# rf_spectrum.net
KiCad netlist of a schematic drawn in EAGLE
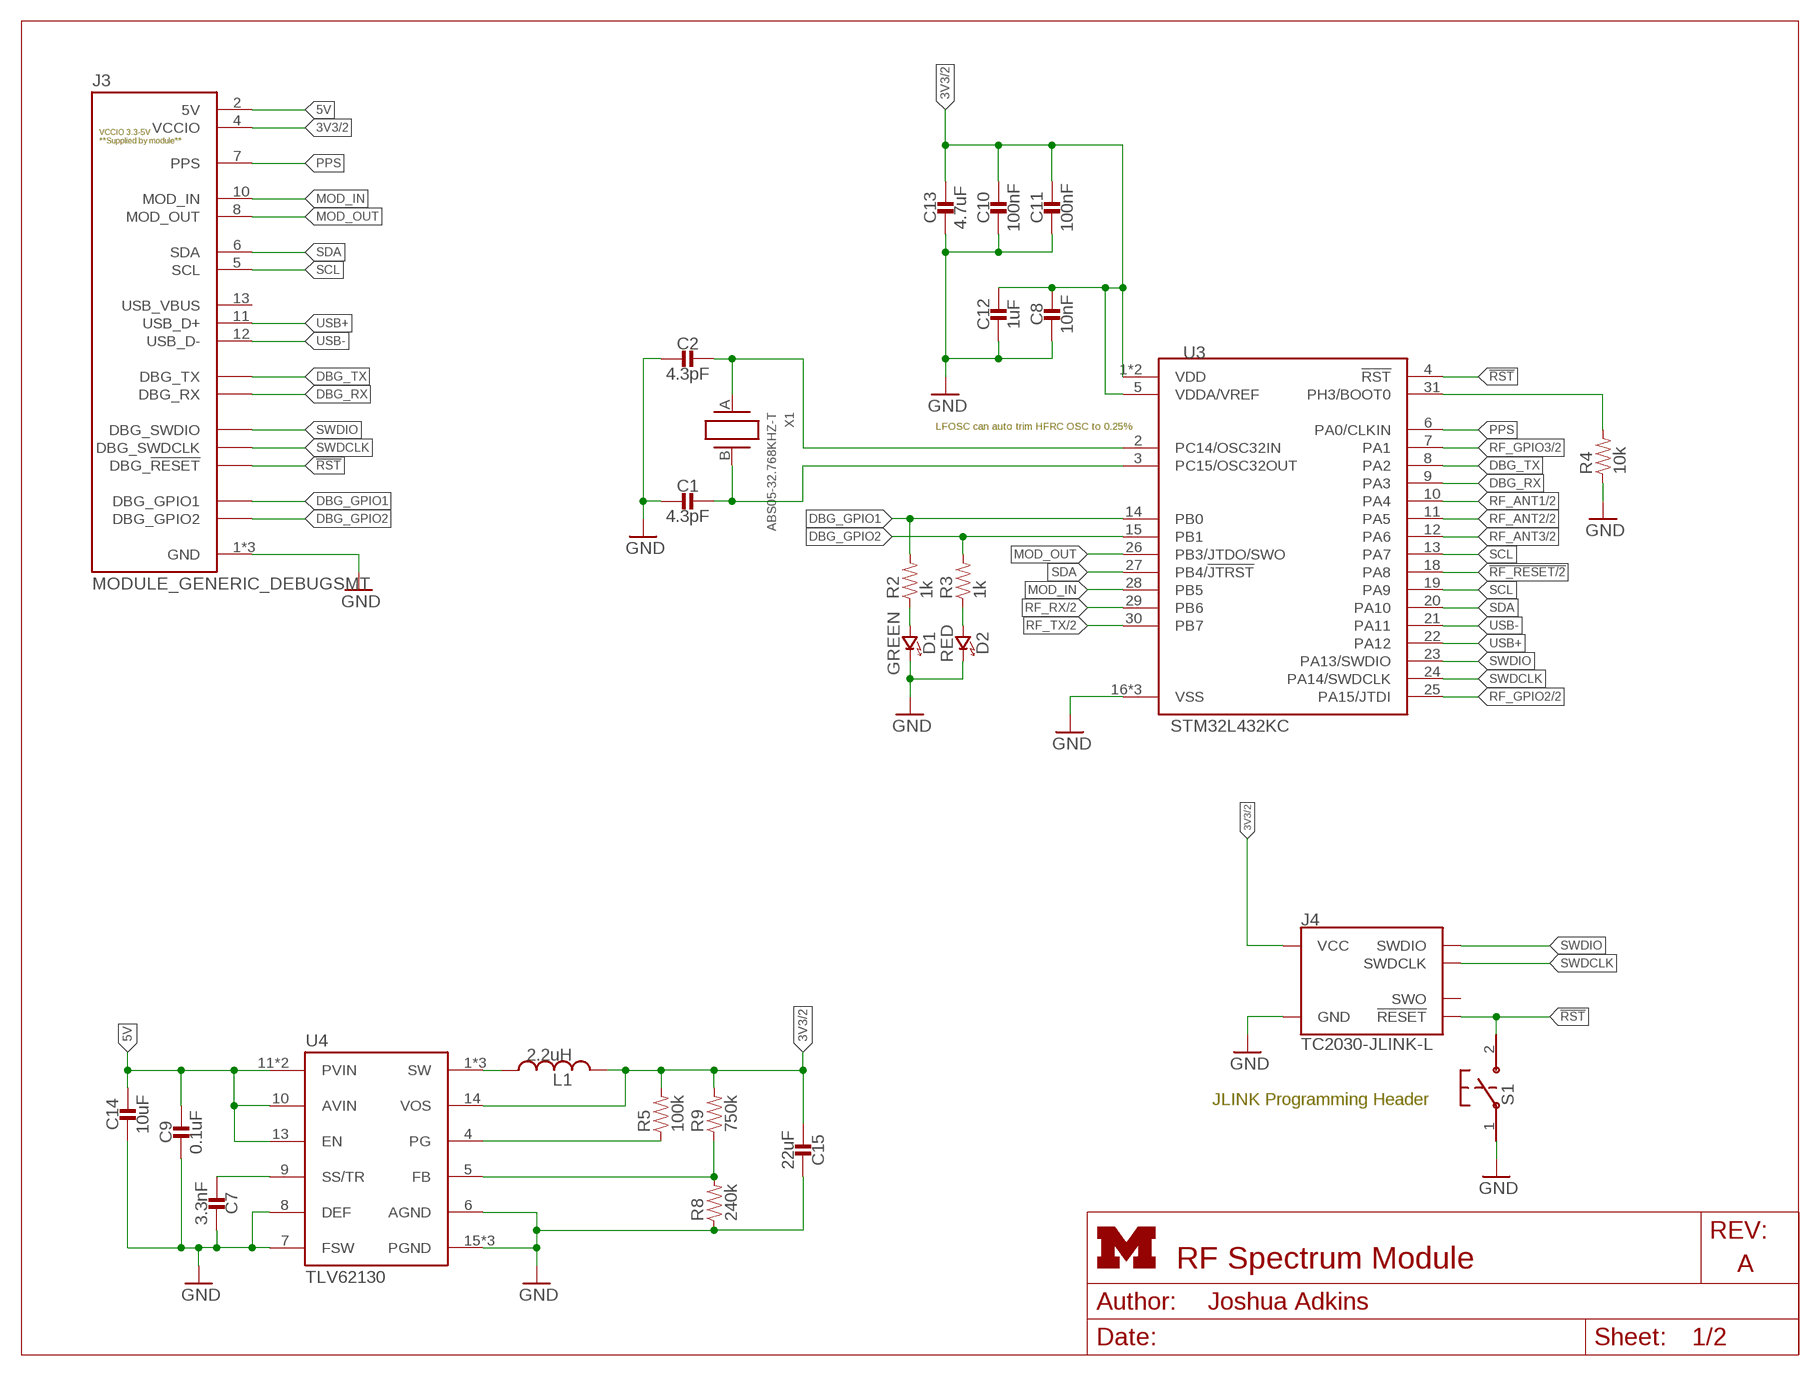
[diagram p0: schematic, sheet 1]
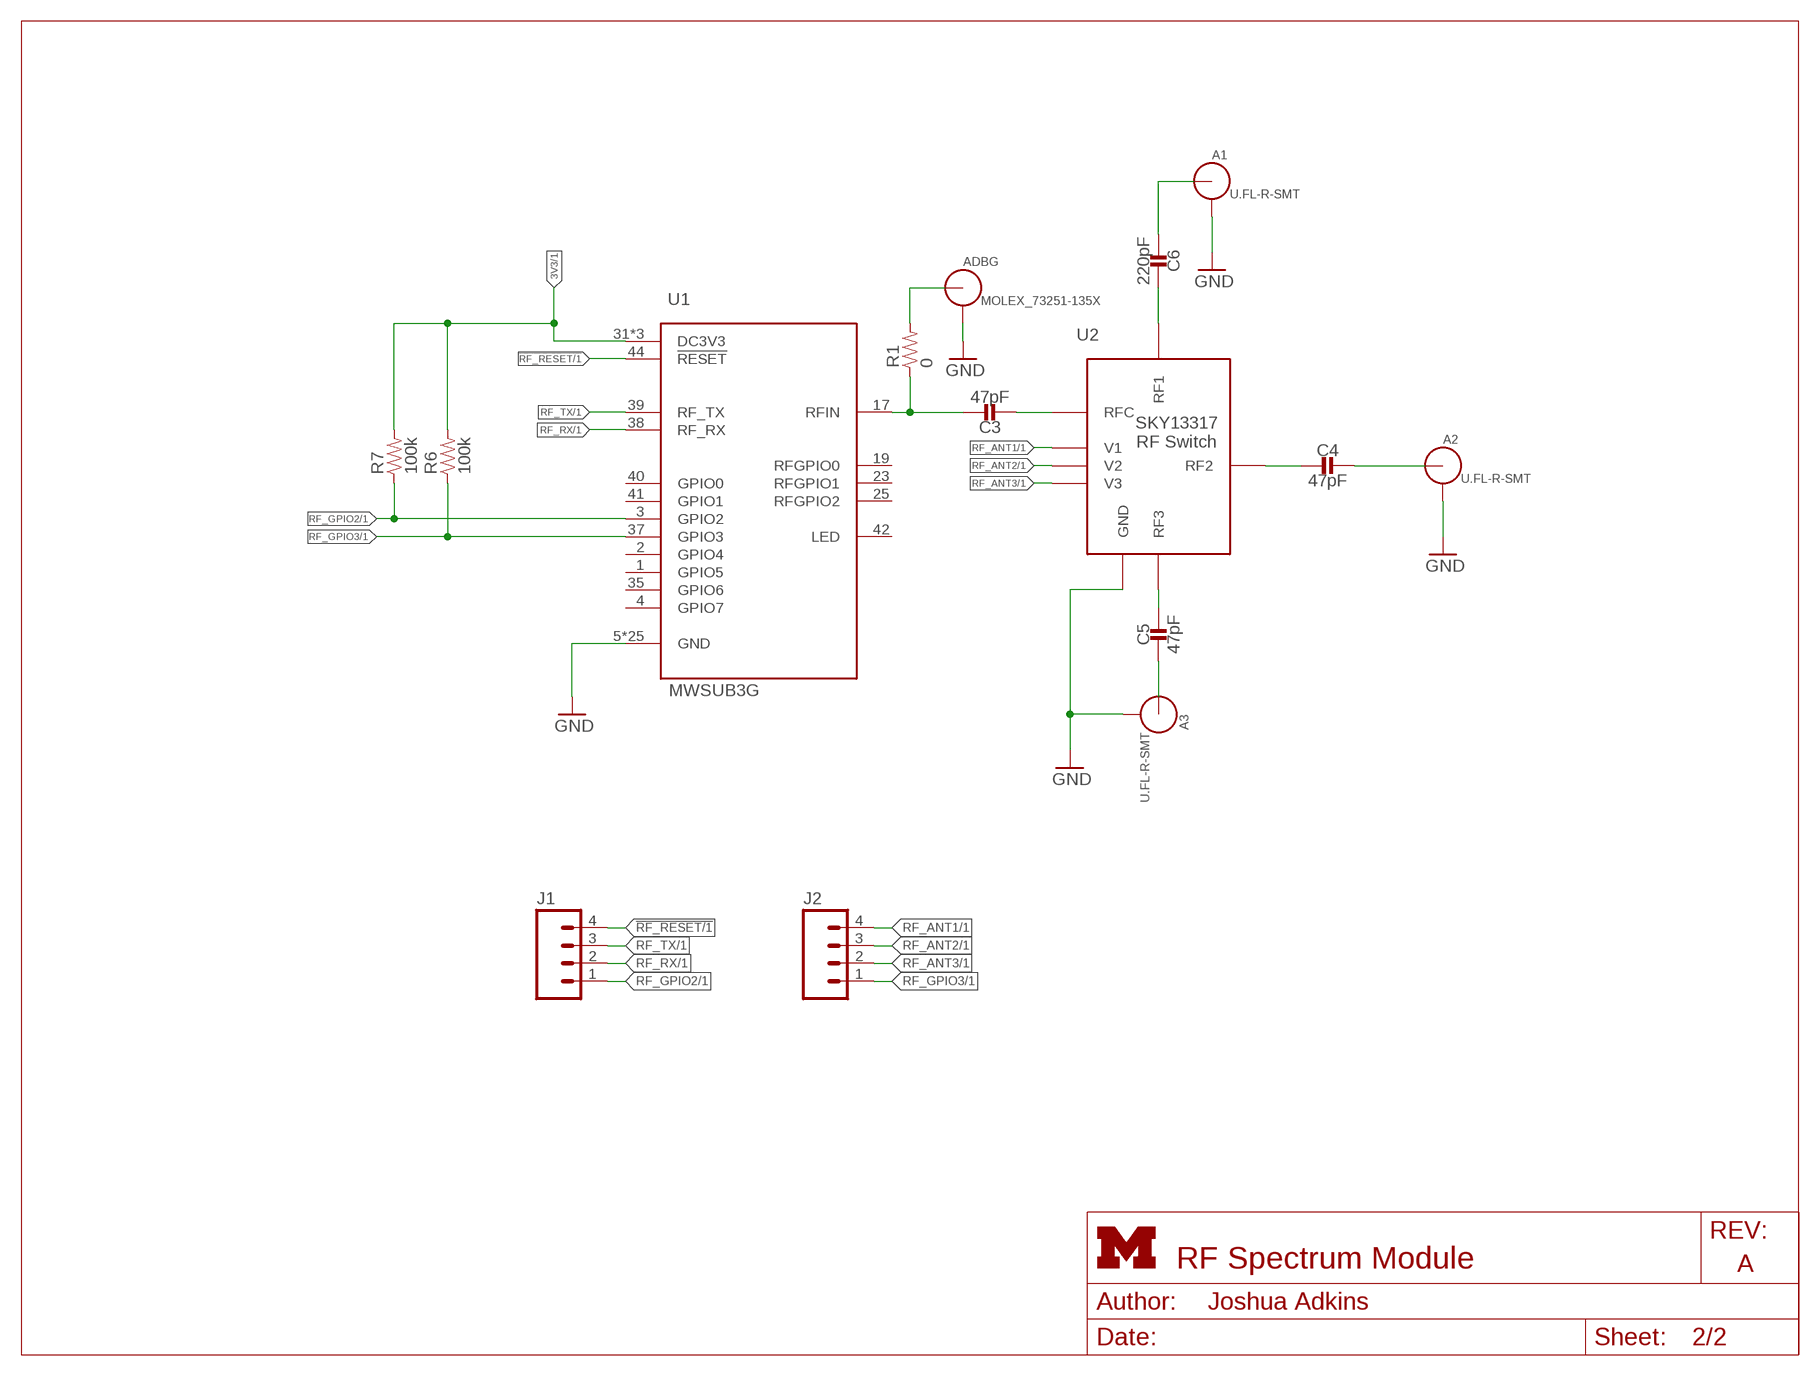
[diagram p1: schematic, sheet 2]

(export (version "E")
  (design (tool "Eeschema 10.0.6"))
  (components
    (comp (ref "A1")
      (value "U.FL-R-SMT")
      (footprint "eagle-import:U.FL_SMT")
      (libsource (lib "eagle-import") (part "U.FL-R-SMT"))
    )
    (comp (ref "A2")
      (value "U.FL-R-SMT")
      (footprint "eagle-import:U.FL_SMT")
      (libsource (lib "eagle-import") (part "U.FL-R-SMT"))
    )
    (comp (ref "A3")
      (value "U.FL-R-SMT")
      (footprint "eagle-import:U.FL_SMT")
      (libsource (lib "eagle-import") (part "U.FL-R-SMT"))
    )
    (comp (ref "ADBG")
      (value "MOLEX_73251-135X")
      (footprint "eagle-import:SMA-J_PCB")
      (libsource (lib "eagle-import") (part "MOLEX_73251-135X"))
    )
    (comp (ref "C3")
      (value "47pF")
      (footprint "eagle-import:0402_CAP")
      (fields (field (name "MF") "Murata"))
      (libsource (lib "eagle-import") (part "CAPACITOR0402_CAP"))
    )
    (comp (ref "C4")
      (value "47pF")
      (footprint "eagle-import:0402_CAP")
      (fields (field (name "MF") "Murata"))
      (libsource (lib "eagle-import") (part "CAPACITOR0402_CAP"))
    )
    (comp (ref "C5")
      (value "47pF")
      (footprint "eagle-import:0402_CAP")
      (fields (field (name "MF") "Murata"))
      (libsource (lib "eagle-import") (part "CAPACITOR0402_CAP"))
    )
    (comp (ref "C6")
      (value "220pF")
      (footprint "eagle-import:0402_CAP")
      (fields (field (name "MF") "Murata"))
      (libsource (lib "eagle-import") (part "CAPACITOR0402_CAP"))
    )
    (comp (ref "J1")
      (value "M04PTH")
      (footprint "eagle-import:1X04")
      (fields (field (name "MF") "Molex"))
      (libsource (lib "eagle-import") (part "M04PTH"))
    )
    (comp (ref "J2")
      (value "M04PTH")
      (footprint "eagle-import:1X04")
      (fields (field (name "MF") "Molex"))
      (libsource (lib "eagle-import") (part "M04PTH"))
    )
    (comp (ref "R1")
      (value "0")
      (footprint "eagle-import:0402_RES")
      (fields (field (name "MF") "Yageo"))
      (libsource (lib "eagle-import") (part "RESISTOR0402_RES"))
    )
    (comp (ref "R6")
      (value "100k")
      (footprint "eagle-import:0402_RES")
      (fields (field (name "MF") "Yageo"))
      (libsource (lib "eagle-import") (part "RESISTOR0402_RES"))
    )
    (comp (ref "R7")
      (value "100k")
      (footprint "eagle-import:0402_RES")
      (fields (field (name "MF") "Yageo"))
      (libsource (lib "eagle-import") (part "RESISTOR0402_RES"))
    )
    (comp (ref "U1")
      (value "MWSUB3G")
      (footprint "eagle-import:MWSUB3G")
      (fields (field (name "MF") "RFExplorer"))
      (libsource (lib "eagle-import") (part "MWSUB3G"))
    )
    (comp (ref "U2")
      (value "SKY13317")
      (footprint "eagle-import:XDFN-8")
      (libsource (lib "eagle-import") (part "SKY13317"))
    )
    (comp (ref "C1")
      (value "4.3pF")
      (footprint "eagle-import:0402_CAP")
      (fields (field (name "MF") "Murata"))
      (libsource (lib "eagle-import") (part "CAPACITOR0402_CAP"))
    )
    (comp (ref "C2")
      (value "4.3pF")
      (footprint "eagle-import:0402_CAP")
      (fields (field (name "MF") "Murata"))
      (libsource (lib "eagle-import") (part "CAPACITOR0402_CAP"))
    )
    (comp (ref "C7")
      (value "3.3nF")
      (footprint "eagle-import:0603_CAP")
      (fields (field (name "MF") "Murata"))
      (libsource (lib "eagle-import") (part "CAPACITOR0603_CAP"))
    )
    (comp (ref "C8")
      (value "10nF")
      (footprint "eagle-import:0402_CAP")
      (fields (field (name "MF") "Murata"))
      (libsource (lib "eagle-import") (part "CAPACITOR0402_CAP"))
    )
    (comp (ref "C9")
      (value "0.1uF")
      (footprint "eagle-import:0603_CAP")
      (fields (field (name "MF") "Murata"))
      (libsource (lib "eagle-import") (part "CAPACITOR0603_CAP"))
    )
    (comp (ref "C10")
      (value "100nF")
      (footprint "eagle-import:0402_CAP")
      (fields (field (name "MF") "Murata"))
      (libsource (lib "eagle-import") (part "CAPACITOR0402_CAP"))
    )
    (comp (ref "C11")
      (value "100nF")
      (footprint "eagle-import:0402_CAP")
      (fields (field (name "MF") "Murata"))
      (libsource (lib "eagle-import") (part "CAPACITOR0402_CAP"))
    )
    (comp (ref "C12")
      (value "1uF")
      (footprint "eagle-import:0402_CAP")
      (fields (field (name "MF") "Murata"))
      (libsource (lib "eagle-import") (part "CAPACITOR0402_CAP"))
    )
    (comp (ref "C13")
      (value "4.7uF")
      (footprint "eagle-import:0402_CAP")
      (fields (field (name "MF") "Murata"))
      (libsource (lib "eagle-import") (part "CAPACITOR0402_CAP"))
    )
    (comp (ref "C14")
      (value "10uF")
      (footprint "eagle-import:0603_CAP")
      (fields (field (name "MF") "Murata"))
      (libsource (lib "eagle-import") (part "CAPACITOR0603_CAP"))
    )
    (comp (ref "C15")
      (value "22uF")
      (footprint "eagle-import:0603_CAP")
      (fields (field (name "MF") "Murata"))
      (libsource (lib "eagle-import") (part "CAPACITOR0603_CAP"))
    )
    (comp (ref "D1")
      (value "GREEN")
      (footprint "eagle-import:LED-0603")
      (fields (field (name "MF") "Lite-ON"))
      (libsource (lib "eagle-import") (part "LED0603"))
    )
    (comp (ref "D2")
      (value "RED")
      (footprint "eagle-import:LED-0603")
      (fields (field (name "MF") "Lite-On"))
      (libsource (lib "eagle-import") (part "LED0603"))
    )
    (comp (ref "J3")
      (value "MODULE_GENERIC_DEBUGSMT")
      (footprint "eagle-import:MODULE_GENERIC_DEBUG_SMT")
      (libsource (lib "eagle-import") (part "MODULE_GENERIC_DEBUGSMT"))
    )
    (comp (ref "J4")
      (value "TC2030-JLINK-L")
      (footprint "eagle-import:TC2030-IDC")
      (libsource (lib "eagle-import") (part "TC2030-JLINK-L"))
    )
    (comp (ref "L1")
      (value "2.2uH")
      (footprint "eagle-import:IHL-1212BZ-11")
      (libsource (lib "eagle-import") (part "INDUCTORIHL"))
    )
    (comp (ref "R2")
      (value "1k")
      (footprint "eagle-import:0402_RES")
      (fields (field (name "MF") "Yageo"))
      (libsource (lib "eagle-import") (part "RESISTOR0402_RES"))
    )
    (comp (ref "R3")
      (value "1k")
      (footprint "eagle-import:0402_RES")
      (fields (field (name "MF") "Yageo"))
      (libsource (lib "eagle-import") (part "RESISTOR0402_RES"))
    )
    (comp (ref "R4")
      (value "10k")
      (footprint "eagle-import:0402_RES")
      (fields (field (name "MF") "Yageo"))
      (libsource (lib "eagle-import") (part "RESISTOR0402_RES"))
    )
    (comp (ref "R5")
      (value "100k")
      (footprint "eagle-import:0603-RES")
      (fields (field (name "MF") "Yageo"))
      (libsource (lib "eagle-import") (part "RESISTOR0603_RES"))
    )
    (comp (ref "R8")
      (value "240k")
      (footprint "eagle-import:0603-RES")
      (fields (field (name "MF") "Yageo"))
      (libsource (lib "eagle-import") (part "RESISTOR0603_RES"))
    )
    (comp (ref "R9")
      (value "750k")
      (footprint "eagle-import:0603-RES")
      (fields (field (name "MF") "Yageo"))
      (libsource (lib "eagle-import") (part "RESISTOR0603_RES"))
    )
    (comp (ref "S1")
      (value "B3U-1000P")
      (footprint "eagle-import:B3U-1000P")
      (libsource (lib "eagle-import") (part "B3U-1000P"))
    )
    (comp (ref "U3")
      (value "STM32L432KC")
      (footprint "eagle-import:UQFN-32")
      (fields (field (name "MF") "STM"))
      (libsource (lib "eagle-import") (part "STM32L432KC"))
    )
    (comp (ref "U4")
      (value "TLV62130")
      (footprint "eagle-import:TQFN-16_3MM")
      (libsource (lib "eagle-import") (part "TLV62130"))
    )
    (comp (ref "X1")
      (value "ABS05-32.768KHZ-T")
      (footprint "eagle-import:ABS05")
      (libsource (lib "eagle-import") (part "ABS05-32.768KHZ-T"))
    )
  )
  (nets
    (net (code "1") (name "3V3") (class "Default")
      (node (ref "C10") (pin "1") (pinfunction "1_1") (pintype "bidirectional"))
      (node (ref "C11") (pin "1") (pinfunction "1_1") (pintype "bidirectional"))
      (node (ref "C12") (pin "1") (pinfunction "1_1") (pintype "bidirectional"))
      (node (ref "C13") (pin "1") (pinfunction "1_1") (pintype "bidirectional"))
      (node (ref "C15") (pin "2") (pinfunction "2_2") (pintype "bidirectional"))
      (node (ref "C8") (pin "1") (pinfunction "1_1") (pintype "bidirectional"))
      (node (ref "J3") (pin "4") (pinfunction "VCCIO_4") (pintype "bidirectional"))
      (node (ref "J4") (pin "1") (pinfunction "VCC_1") (pintype "bidirectional"))
      (node (ref "L1") (pin "P$2") (pinfunction "2_P$2") (pintype "bidirectional"))
      (node (ref "R5") (pin "2") (pinfunction "2_2") (pintype "passive"))
      (node (ref "R6") (pin "2") (pinfunction "2_2") (pintype "passive"))
      (node (ref "R7") (pin "2") (pinfunction "2_2") (pintype "passive"))
      (node (ref "R9") (pin "2") (pinfunction "2_2") (pintype "passive"))
      (node (ref "U1") (pin "31") (pinfunction "DC3V3_31") (pintype "bidirectional"))
      (node (ref "U1") (pin "32") (pinfunction "DC3V3_32") (pintype "bidirectional"))
      (node (ref "U1") (pin "33") (pinfunction "DC3V3_33") (pintype "bidirectional"))
      (node (ref "U3") (pin "1") (pinfunction "VDD_1") (pintype "bidirectional"))
      (node (ref "U3") (pin "17") (pinfunction "VDD_17") (pintype "bidirectional"))
      (node (ref "U3") (pin "5") (pinfunction "VDDA/VREF_5") (pintype "bidirectional"))
      (node (ref "U4") (pin "14") (pinfunction "VOS_14") (pintype "bidirectional"))
    )
    (net (code "2") (name "5V") (class "Default")
      (node (ref "C14") (pin "1") (pinfunction "1_1") (pintype "bidirectional"))
      (node (ref "C9") (pin "1") (pinfunction "1_1") (pintype "bidirectional"))
      (node (ref "J3") (pin "2") (pinfunction "5V_2") (pintype "bidirectional"))
      (node (ref "U4") (pin "10") (pinfunction "AVIN_10") (pintype "bidirectional"))
      (node (ref "U4") (pin "11") (pinfunction "PVIN_11") (pintype "bidirectional"))
      (node (ref "U4") (pin "12") (pinfunction "PVIN_12") (pintype "bidirectional"))
      (node (ref "U4") (pin "13") (pinfunction "EN_13") (pintype "bidirectional"))
    )
    (net (code "3") (name "DBG_GPIO1") (class "Default")
      (node (ref "J3") (pin "16") (pinfunction "DBG_GPIO1_16") (pintype "bidirectional"))
      (node (ref "R2") (pin "2") (pinfunction "2_2") (pintype "passive"))
      (node (ref "U3") (pin "14") (pinfunction "PB0_14") (pintype "bidirectional"))
    )
    (net (code "4") (name "DBG_GPIO2") (class "Default")
      (node (ref "J3") (pin "19") (pinfunction "DBG_GPIO2_19") (pintype "bidirectional"))
      (node (ref "R3") (pin "2") (pinfunction "2_2") (pintype "passive"))
      (node (ref "U3") (pin "15") (pinfunction "PB1_15") (pintype "bidirectional"))
    )
    (net (code "5") (name "DBG_RX") (class "Default")
      (node (ref "J3") (pin "18") (pinfunction "DBG_RX_18") (pintype "bidirectional"))
      (node (ref "U3") (pin "9") (pinfunction "PA3_9") (pintype "bidirectional"))
    )
    (net (code "6") (name "DBG_TX") (class "Default")
      (node (ref "J3") (pin "17") (pinfunction "DBG_TX_17") (pintype "bidirectional"))
      (node (ref "U3") (pin "8") (pinfunction "PA2_8") (pintype "bidirectional"))
    )
    (net (code "7") (name "GND") (class "Default")
      (node (ref "A1") (pin "GND1") (pinfunction "P$2_GND1") (pintype "bidirectional"))
      (node (ref "A1") (pin "GND2") (pinfunction "P$2_GND2") (pintype "bidirectional"))
      (node (ref "A2") (pin "GND1") (pinfunction "P$2_GND1") (pintype "bidirectional"))
      (node (ref "A2") (pin "GND2") (pinfunction "P$2_GND2") (pintype "bidirectional"))
      (node (ref "A3") (pin "GND1") (pinfunction "P$2_GND1") (pintype "bidirectional"))
      (node (ref "A3") (pin "GND2") (pinfunction "P$2_GND2") (pintype "bidirectional"))
      (node (ref "ADBG") (pin "2") (pinfunction "P$2_2") (pintype "bidirectional"))
      (node (ref "ADBG") (pin "3") (pinfunction "P$2_3") (pintype "bidirectional"))
      (node (ref "ADBG") (pin "4") (pinfunction "P$2_4") (pintype "bidirectional"))
      (node (ref "ADBG") (pin "5") (pinfunction "P$2_5") (pintype "bidirectional"))
      (node (ref "C1") (pin "2") (pinfunction "2_2") (pintype "bidirectional"))
      (node (ref "C10") (pin "2") (pinfunction "2_2") (pintype "bidirectional"))
      (node (ref "C11") (pin "2") (pinfunction "2_2") (pintype "bidirectional"))
      (node (ref "C12") (pin "2") (pinfunction "2_2") (pintype "bidirectional"))
      (node (ref "C13") (pin "2") (pinfunction "2_2") (pintype "bidirectional"))
      (node (ref "C14") (pin "2") (pinfunction "2_2") (pintype "bidirectional"))
      (node (ref "C15") (pin "1") (pinfunction "1_1") (pintype "bidirectional"))
      (node (ref "C2") (pin "2") (pinfunction "2_2") (pintype "bidirectional"))
      (node (ref "C7") (pin "1") (pinfunction "1_1") (pintype "bidirectional"))
      (node (ref "C8") (pin "2") (pinfunction "2_2") (pintype "bidirectional"))
      (node (ref "C9") (pin "2") (pinfunction "2_2") (pintype "bidirectional"))
      (node (ref "D1") (pin "C") (pinfunction "CATHODE_C") (pintype "bidirectional"))
      (node (ref "D2") (pin "C") (pinfunction "CATHODE_C") (pintype "bidirectional"))
      (node (ref "J3") (pin "1") (pinfunction "GND_1") (pintype "bidirectional"))
      (node (ref "J3") (pin "14") (pinfunction "GND_14") (pintype "bidirectional"))
      (node (ref "J3") (pin "15") (pinfunction "GND_15") (pintype "bidirectional"))
      (node (ref "J4") (pin "5") (pinfunction "GND_5") (pintype "bidirectional"))
      (node (ref "R4") (pin "1") (pinfunction "1_1") (pintype "passive"))
      (node (ref "R8") (pin "1") (pinfunction "1_1") (pintype "passive"))
      (node (ref "S1") (pin "1") (pinfunction "P$1_1") (pintype "passive"))
      (node (ref "U1") (pin "10") (pinfunction "GND_10") (pintype "bidirectional"))
      (node (ref "U1") (pin "11") (pinfunction "GND_11") (pintype "bidirectional"))
      (node (ref "U1") (pin "12") (pinfunction "GND_12") (pintype "bidirectional"))
      (node (ref "U1") (pin "13") (pinfunction "GND_13") (pintype "bidirectional"))
      (node (ref "U1") (pin "14") (pinfunction "GND_14") (pintype "bidirectional"))
      (node (ref "U1") (pin "15") (pinfunction "GND_15") (pintype "bidirectional"))
      (node (ref "U1") (pin "16") (pinfunction "GND_16") (pintype "bidirectional"))
      (node (ref "U1") (pin "18") (pinfunction "GND_18") (pintype "bidirectional"))
      (node (ref "U1") (pin "20") (pinfunction "GND_20") (pintype "bidirectional"))
      (node (ref "U1") (pin "21") (pinfunction "GND_21") (pintype "bidirectional"))
      (node (ref "U1") (pin "22") (pinfunction "GND_22") (pintype "bidirectional"))
      (node (ref "U1") (pin "24") (pinfunction "GND_24") (pintype "bidirectional"))
      (node (ref "U1") (pin "26") (pinfunction "GND_26") (pintype "bidirectional"))
      (node (ref "U1") (pin "27") (pinfunction "GND_27") (pintype "bidirectional"))
      (node (ref "U1") (pin "28") (pinfunction "GND_28") (pintype "bidirectional"))
      (node (ref "U1") (pin "29") (pinfunction "GND_29") (pintype "bidirectional"))
      (node (ref "U1") (pin "34") (pinfunction "GND_34") (pintype "bidirectional"))
      (node (ref "U1") (pin "43") (pinfunction "GND_43") (pintype "bidirectional"))
      (node (ref "U1") (pin "45") (pinfunction "GND_45") (pintype "bidirectional"))
      (node (ref "U1") (pin "46") (pinfunction "GND_46") (pintype "bidirectional"))
      (node (ref "U1") (pin "5") (pinfunction "GND_5") (pintype "bidirectional"))
      (node (ref "U1") (pin "6") (pinfunction "GND_6") (pintype "bidirectional"))
      (node (ref "U1") (pin "7") (pinfunction "GND_7") (pintype "bidirectional"))
      (node (ref "U1") (pin "8") (pinfunction "GND_8") (pintype "bidirectional"))
      (node (ref "U1") (pin "9") (pinfunction "GND_9") (pintype "bidirectional"))
      (node (ref "U2") (pin "P$1") (pinfunction "GND_P$1") (pintype "bidirectional"))
      (node (ref "U3") (pin "16") (pinfunction "VSS_16") (pintype "bidirectional"))
      (node (ref "U3") (pin "32") (pinfunction "VSS_32") (pintype "bidirectional"))
      (node (ref "U3") (pin "THERMAL") (pinfunction "VSS_THERMAL") (pintype "bidirectional"))
      (node (ref "U4") (pin "15") (pinfunction "PGND_15") (pintype "bidirectional"))
      (node (ref "U4") (pin "16") (pinfunction "PGND_16") (pintype "bidirectional"))
      (node (ref "U4") (pin "6") (pinfunction "AGND_6") (pintype "bidirectional"))
      (node (ref "U4") (pin "7") (pinfunction "FSW_7") (pintype "bidirectional"))
      (node (ref "U4") (pin "8") (pinfunction "DEF_8") (pintype "bidirectional"))
      (node (ref "U4") (pin "GND") (pinfunction "PGND_GND") (pintype "bidirectional"))
    )
    (net (code "8") (name "MOD_IN") (class "Default")
      (node (ref "J3") (pin "10") (pinfunction "MOD_IN_10") (pintype "bidirectional"))
      (node (ref "U3") (pin "28") (pinfunction "PB5_28") (pintype "bidirectional"))
    )
    (net (code "9") (name "MOD_OUT") (class "Default")
      (node (ref "J3") (pin "8") (pinfunction "MOD_OUT_8") (pintype "bidirectional"))
      (node (ref "U3") (pin "26") (pinfunction "PB3/JTDO/SWO_26") (pintype "bidirectional"))
    )
    (net (code "10") (name "Net-(A1-ANT)") (class "Default")
      (node (ref "A1") (pin "SIG") (pinfunction "ANT_SIG") (pintype "bidirectional"))
      (node (ref "C6") (pin "2") (pinfunction "2_2") (pintype "bidirectional"))
    )
    (net (code "11") (name "Net-(A2-ANT)") (class "Default")
      (node (ref "A2") (pin "SIG") (pinfunction "ANT_SIG") (pintype "bidirectional"))
      (node (ref "C4") (pin "1") (pinfunction "1_1") (pintype "bidirectional"))
    )
    (net (code "12") (name "Net-(A3-ANT)") (class "Default")
      (node (ref "A3") (pin "SIG") (pinfunction "ANT_SIG") (pintype "bidirectional"))
      (node (ref "C5") (pin "2") (pinfunction "2_2") (pintype "bidirectional"))
    )
    (net (code "13") (name "Net-(ADBG-ANT)") (class "Default")
      (node (ref "ADBG") (pin "1") (pinfunction "ANT_1") (pintype "bidirectional"))
      (node (ref "R1") (pin "2") (pinfunction "2_2") (pintype "passive"))
    )
    (net (code "14") (name "Net-(D1-ANODE)") (class "Default")
      (node (ref "D1") (pin "A") (pinfunction "ANODE_A") (pintype "bidirectional"))
      (node (ref "R2") (pin "1") (pinfunction "1_1") (pintype "passive"))
    )
    (net (code "15") (name "Net-(D2-ANODE)") (class "Default")
      (node (ref "D2") (pin "A") (pinfunction "ANODE_A") (pintype "bidirectional"))
      (node (ref "R3") (pin "1") (pinfunction "1_1") (pintype "passive"))
    )
    (net (code "16") (name "Net-(L1-1)") (class "Default")
      (node (ref "L1") (pin "P$1") (pinfunction "1_P$1") (pintype "bidirectional"))
      (node (ref "U4") (pin "1") (pinfunction "SW_1") (pintype "bidirectional"))
      (node (ref "U4") (pin "2") (pinfunction "SW_2") (pintype "bidirectional"))
      (node (ref "U4") (pin "3") (pinfunction "SW_3") (pintype "bidirectional"))
    )
    (net (code "17") (name "Net-(U1-RFIN)") (class "Default")
      (node (ref "C3") (pin "1") (pinfunction "1_1") (pintype "bidirectional"))
      (node (ref "R1") (pin "1") (pinfunction "1_1") (pintype "passive"))
      (node (ref "U1") (pin "17") (pinfunction "RFIN_17") (pintype "bidirectional"))
    )
    (net (code "18") (name "Net-(U2-RF1)") (class "Default")
      (node (ref "C6") (pin "1") (pinfunction "1_1") (pintype "bidirectional"))
      (node (ref "U2") (pin "4") (pinfunction "RF1_4") (pintype "bidirectional"))
    )
    (net (code "19") (name "Net-(U2-RF2)") (class "Default")
      (node (ref "C4") (pin "2") (pinfunction "2_2") (pintype "bidirectional"))
      (node (ref "U2") (pin "5") (pinfunction "RF2_5") (pintype "bidirectional"))
    )
    (net (code "20") (name "Net-(U2-RF3)") (class "Default")
      (node (ref "C5") (pin "1") (pinfunction "1_1") (pintype "bidirectional"))
      (node (ref "U2") (pin "8") (pinfunction "RF3_8") (pintype "bidirectional"))
    )
    (net (code "21") (name "Net-(U2-RFC)") (class "Default")
      (node (ref "C3") (pin "2") (pinfunction "2_2") (pintype "bidirectional"))
      (node (ref "U2") (pin "1") (pinfunction "RFC_1") (pintype "bidirectional"))
    )
    (net (code "22") (name "Net-(U3-PC14{slash}OSC32IN)") (class "Default")
      (node (ref "C2") (pin "1") (pinfunction "1_1") (pintype "bidirectional"))
      (node (ref "U3") (pin "2") (pinfunction "PC14/OSC32IN_2") (pintype "bidirectional"))
      (node (ref "X1") (pin "A") (pinfunction "1_A") (pintype "bidirectional"))
    )
    (net (code "23") (name "Net-(U3-PC15{slash}OSC32OUT)") (class "Default")
      (node (ref "C1") (pin "1") (pinfunction "1_1") (pintype "bidirectional"))
      (node (ref "U3") (pin "3") (pinfunction "PC15/OSC32OUT_3") (pintype "bidirectional"))
      (node (ref "X1") (pin "B") (pinfunction "2_B") (pintype "bidirectional"))
    )
    (net (code "24") (name "Net-(U3-PH3{slash}BOOT0)") (class "Default")
      (node (ref "R4") (pin "2") (pinfunction "2_2") (pintype "passive"))
      (node (ref "U3") (pin "31") (pinfunction "PH3/BOOT0_31") (pintype "bidirectional"))
    )
    (net (code "25") (name "Net-(U4-FB)") (class "Default")
      (node (ref "R8") (pin "2") (pinfunction "2_2") (pintype "passive"))
      (node (ref "R9") (pin "1") (pinfunction "1_1") (pintype "passive"))
      (node (ref "U4") (pin "5") (pinfunction "FB_5") (pintype "bidirectional"))
    )
    (net (code "26") (name "Net-(U4-PG)") (class "Default")
      (node (ref "R5") (pin "1") (pinfunction "1_1") (pintype "passive"))
      (node (ref "U4") (pin "4") (pinfunction "PG_4") (pintype "bidirectional"))
    )
    (net (code "27") (name "Net-(U4-SS{slash}TR)") (class "Default")
      (node (ref "C7") (pin "2") (pinfunction "2_2") (pintype "bidirectional"))
      (node (ref "U4") (pin "9") (pinfunction "SS/TR_9") (pintype "bidirectional"))
    )
    (net (code "28") (name "PPS") (class "Default")
      (node (ref "J3") (pin "7") (pinfunction "PPS_7") (pintype "bidirectional"))
      (node (ref "U3") (pin "6") (pinfunction "PA0/CLKIN_6") (pintype "bidirectional"))
    )
    (net (code "29") (name "RF_ANT1") (class "Default")
      (node (ref "J2") (pin "4") (pinfunction "4_4") (pintype "passive"))
      (node (ref "U2") (pin "3") (pinfunction "V1_3") (pintype "bidirectional"))
      (node (ref "U3") (pin "10") (pinfunction "PA4_10") (pintype "bidirectional"))
    )
    (net (code "30") (name "RF_ANT2") (class "Default")
      (node (ref "J2") (pin "3") (pinfunction "3_3") (pintype "passive"))
      (node (ref "U2") (pin "6") (pinfunction "V2_6") (pintype "bidirectional"))
      (node (ref "U3") (pin "11") (pinfunction "PA5_11") (pintype "bidirectional"))
    )
    (net (code "31") (name "RF_ANT3") (class "Default")
      (node (ref "J2") (pin "2") (pinfunction "2_2") (pintype "passive"))
      (node (ref "U2") (pin "7") (pinfunction "V3_7") (pintype "bidirectional"))
      (node (ref "U3") (pin "12") (pinfunction "PA6_12") (pintype "bidirectional"))
    )
    (net (code "32") (name "RF_GPIO2") (class "Default")
      (node (ref "J1") (pin "1") (pinfunction "1_1") (pintype "passive"))
      (node (ref "R7") (pin "1") (pinfunction "1_1") (pintype "passive"))
      (node (ref "U1") (pin "3") (pinfunction "GPIO2_3") (pintype "bidirectional"))
      (node (ref "U3") (pin "25") (pinfunction "PA15/JTDI_25") (pintype "bidirectional"))
    )
    (net (code "33") (name "RF_GPIO3") (class "Default")
      (node (ref "J2") (pin "1") (pinfunction "1_1") (pintype "passive"))
      (node (ref "R6") (pin "1") (pinfunction "1_1") (pintype "passive"))
      (node (ref "U1") (pin "37") (pinfunction "GPIO3_37") (pintype "bidirectional"))
      (node (ref "U3") (pin "7") (pinfunction "PA1_7") (pintype "bidirectional"))
    )
    (net (code "34") (name "RF_RX") (class "Default")
      (node (ref "J1") (pin "2") (pinfunction "2_2") (pintype "passive"))
      (node (ref "U1") (pin "38") (pinfunction "RF_RX_38") (pintype "bidirectional"))
      (node (ref "U3") (pin "29") (pinfunction "PB6_29") (pintype "bidirectional"))
    )
    (net (code "35") (name "RF_TX") (class "Default")
      (node (ref "J1") (pin "3") (pinfunction "3_3") (pintype "passive"))
      (node (ref "U1") (pin "39") (pinfunction "RF_TX_39") (pintype "bidirectional"))
      (node (ref "U3") (pin "30") (pinfunction "PB7_30") (pintype "bidirectional"))
    )
    (net (code "36") (name "SCL") (class "Default")
      (node (ref "J3") (pin "5") (pinfunction "SCL_5") (pintype "bidirectional"))
      (node (ref "U3") (pin "13") (pinfunction "PA7_13") (pintype "bidirectional"))
      (node (ref "U3") (pin "19") (pinfunction "PA9_19") (pintype "bidirectional"))
    )
    (net (code "37") (name "SDA") (class "Default")
      (node (ref "J3") (pin "6") (pinfunction "SDA_6") (pintype "bidirectional"))
      (node (ref "U3") (pin "20") (pinfunction "PA10_20") (pintype "bidirectional"))
      (node (ref "U3") (pin "27") (pinfunction "PB4/~{JTRST}_27") (pintype "bidirectional"))
    )
    (net (code "38") (name "SWDCLK") (class "Default")
      (node (ref "J3") (pin "21") (pinfunction "DBG_SWDCLK_21") (pintype "bidirectional"))
      (node (ref "J4") (pin "4") (pinfunction "SWDCLK_4") (pintype "bidirectional"))
      (node (ref "U3") (pin "24") (pinfunction "PA14/SWDCLK_24") (pintype "bidirectional"))
    )
    (net (code "39") (name "SWDIO") (class "Default")
      (node (ref "J3") (pin "22") (pinfunction "DBG_SWDIO_22") (pintype "bidirectional"))
      (node (ref "J4") (pin "2") (pinfunction "SWDIO_2") (pintype "bidirectional"))
      (node (ref "U3") (pin "23") (pinfunction "PA13/SWDIO_23") (pintype "bidirectional"))
    )
    (net (code "40") (name "USB+") (class "Default")
      (node (ref "J3") (pin "11") (pinfunction "USB_D+_11") (pintype "bidirectional"))
      (node (ref "U3") (pin "22") (pinfunction "PA12_22") (pintype "bidirectional"))
    )
    (net (code "41") (name "USB-") (class "Default")
      (node (ref "J3") (pin "12") (pinfunction "USB_D-_12") (pintype "bidirectional"))
      (node (ref "U3") (pin "21") (pinfunction "PA11_21") (pintype "bidirectional"))
    )
    (net (code "42") (name "unconnected-(J3-USB_VBUS-Pad13)") (class "Default")
      (node (ref "J3") (pin "13") (pinfunction "USB_VBUS_13") (pintype "bidirectional"))
    )
    (net (code "43") (name "unconnected-(J4-SWO-Pad6)") (class "Default")
      (node (ref "J4") (pin "6") (pinfunction "SWO_6") (pintype "bidirectional"))
    )
    (net (code "44") (name "unconnected-(U1-GPIO0-Pad40)") (class "Default")
      (node (ref "U1") (pin "40") (pinfunction "GPIO0_40") (pintype "bidirectional"))
    )
    (net (code "45") (name "unconnected-(U1-GPIO1-Pad41)") (class "Default")
      (node (ref "U1") (pin "41") (pinfunction "GPIO1_41") (pintype "bidirectional"))
    )
    (net (code "46") (name "unconnected-(U1-GPIO4-Pad2)") (class "Default")
      (node (ref "U1") (pin "2") (pinfunction "GPIO4_2") (pintype "bidirectional"))
    )
    (net (code "47") (name "unconnected-(U1-GPIO5-Pad1)") (class "Default")
      (node (ref "U1") (pin "1") (pinfunction "GPIO5_1") (pintype "bidirectional"))
    )
    (net (code "48") (name "unconnected-(U1-GPIO6-Pad35)") (class "Default")
      (node (ref "U1") (pin "35") (pinfunction "GPIO6_35") (pintype "bidirectional"))
    )
    (net (code "49") (name "unconnected-(U1-GPIO7-Pad4)") (class "Default")
      (node (ref "U1") (pin "4") (pinfunction "GPIO7_4") (pintype "bidirectional"))
    )
    (net (code "50") (name "unconnected-(U1-LED-Pad42)") (class "Default")
      (node (ref "U1") (pin "42") (pinfunction "LED_42") (pintype "bidirectional"))
    )
    (net (code "51") (name "unconnected-(U1-RFGPIO0-Pad19)") (class "Default")
      (node (ref "U1") (pin "19") (pinfunction "RFGPIO0_19") (pintype "bidirectional"))
    )
    (net (code "52") (name "unconnected-(U1-RFGPIO1-Pad23)") (class "Default")
      (node (ref "U1") (pin "23") (pinfunction "RFGPIO1_23") (pintype "bidirectional"))
    )
    (net (code "53") (name "unconnected-(U1-RFGPIO2-Pad25)") (class "Default")
      (node (ref "U1") (pin "25") (pinfunction "RFGPIO2_25") (pintype "bidirectional"))
    )
    (net (code "54") (name "~{RF_RESET}") (class "Default")
      (node (ref "J1") (pin "4") (pinfunction "4_4") (pintype "passive"))
      (node (ref "U1") (pin "44") (pinfunction "~{RESET}_44") (pintype "bidirectional"))
      (node (ref "U3") (pin "18") (pinfunction "PA8_18") (pintype "bidirectional"))
    )
    (net (code "55") (name "~{RST}") (class "Default")
      (node (ref "J3") (pin "20") (pinfunction "DBG_~{RESET}_20") (pintype "bidirectional"))
      (node (ref "J4") (pin "3") (pinfunction "~{RESET}_3") (pintype "bidirectional"))
      (node (ref "S1") (pin "2") (pinfunction "P$2_2") (pintype "passive"))
      (node (ref "U3") (pin "4") (pinfunction "~{RST}_4") (pintype "bidirectional"))
    )
  )
)
